# Test_board_v3.net
KiCad netlist of a schematic drawn in EAGLE
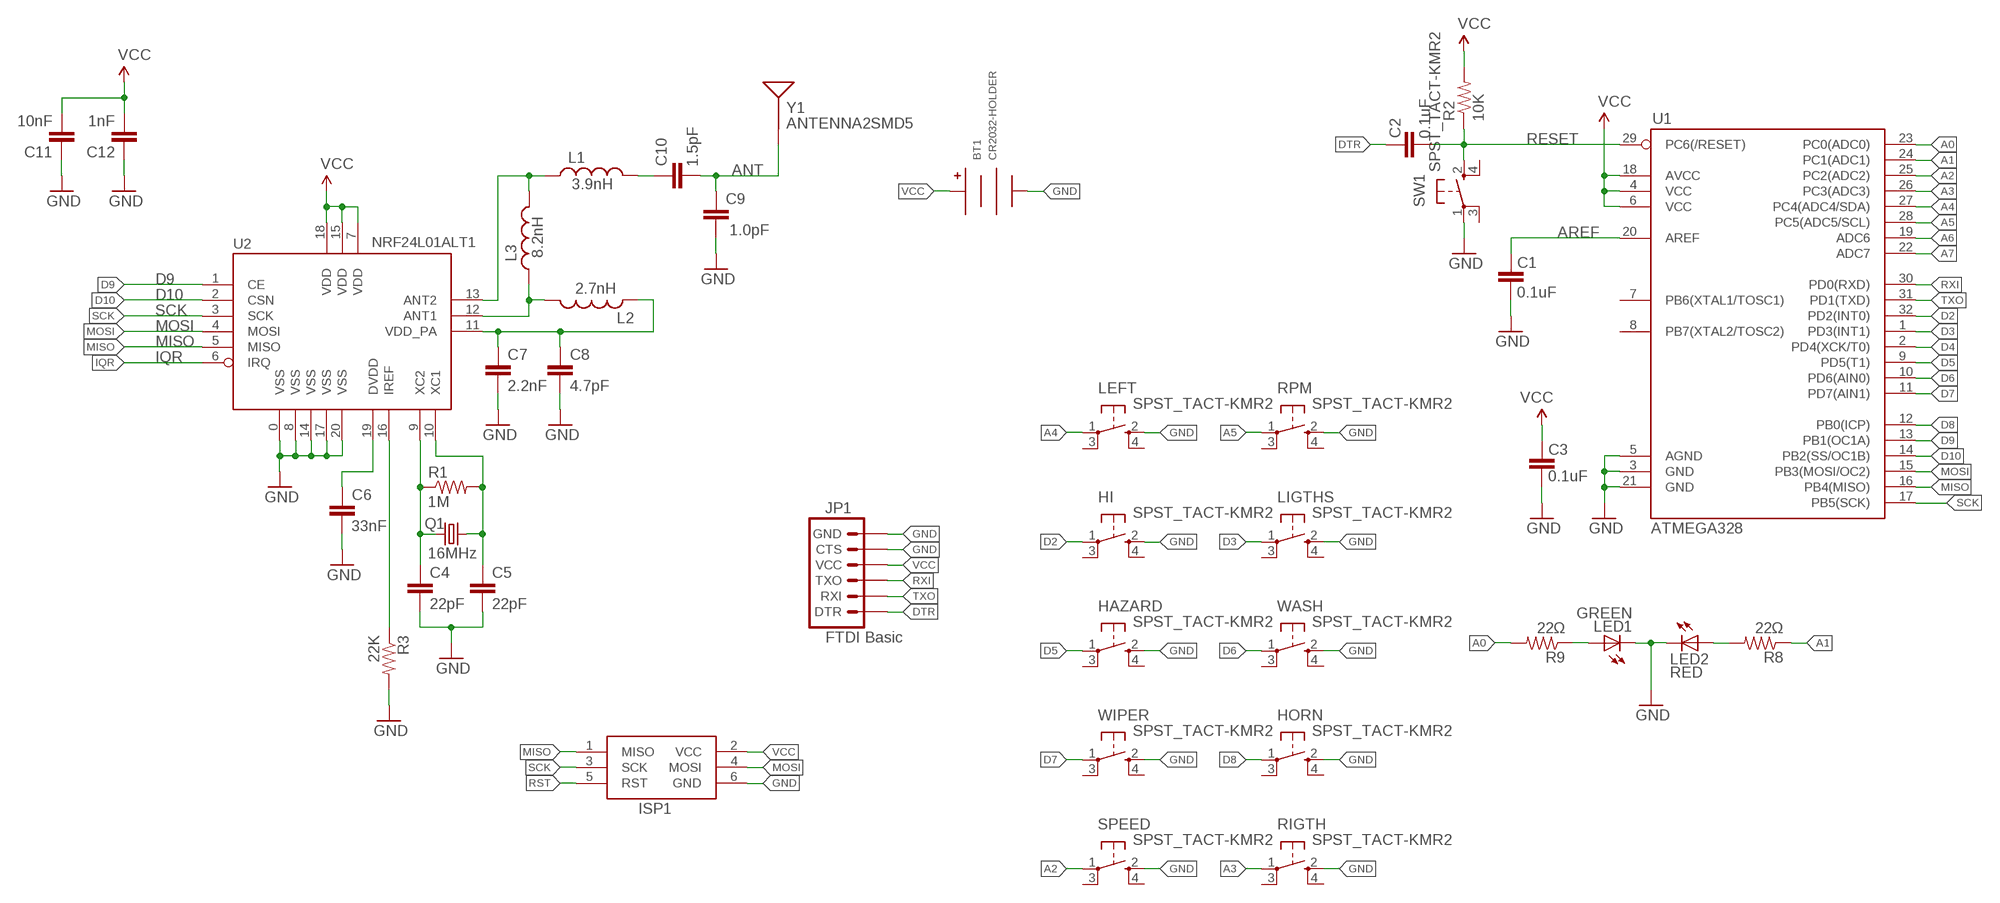
[diagram p0: schematic, sheet 1]

(export (version "E")
  (design (tool "Eeschema 10.0.6"))
  (components
    (comp (ref "BT1")
      (value "CR2032-HOLDER")
      (footprint "eagle-import:CH28-2032LF")
      (libsource (lib "eagle-import") (part "CR2032-HOLDER"))
    )
    (comp (ref "C1")
      (value "0.1uF")
      (footprint "eagle-import:0402-CAP")
      (libsource (lib "eagle-import") (part "CAP0402-CAP"))
    )
    (comp (ref "C2")
      (value "0.1uF")
      (footprint "eagle-import:0402-CAP")
      (libsource (lib "eagle-import") (part "CAP0402-CAP"))
    )
    (comp (ref "C3")
      (value "0.1uF")
      (footprint "eagle-import:0402-CAP")
      (libsource (lib "eagle-import") (part "CAP0402-CAP"))
    )
    (comp (ref "C4")
      (value "22pF")
      (footprint "eagle-import:0402-CAP")
      (libsource (lib "eagle-import") (part "CAP0402-CAP"))
    )
    (comp (ref "C5")
      (value "22pF")
      (footprint "eagle-import:0402-CAP")
      (libsource (lib "eagle-import") (part "CAP0402-CAP"))
    )
    (comp (ref "C6")
      (value "33nF")
      (footprint "eagle-import:0402-CAP")
      (libsource (lib "eagle-import") (part "CAP0402-CAP"))
    )
    (comp (ref "C7")
      (value "2.2nF")
      (footprint "eagle-import:0402-CAP")
      (libsource (lib "eagle-import") (part "CAP0402-CAP"))
    )
    (comp (ref "C8")
      (value "4.7pF")
      (footprint "eagle-import:0402-CAP")
      (libsource (lib "eagle-import") (part "CAP0402-CAP"))
    )
    (comp (ref "C9")
      (value "1.0pF")
      (footprint "eagle-import:0402-CAP")
      (libsource (lib "eagle-import") (part "CAP0402-CAP"))
    )
    (comp (ref "C10")
      (value "1.5pF")
      (footprint "eagle-import:0402-CAP")
      (libsource (lib "eagle-import") (part "CAP0402-CAP"))
    )
    (comp (ref "C11")
      (value "10nF")
      (footprint "eagle-import:0402-CAP")
      (libsource (lib "eagle-import") (part "CAP0402-CAP"))
    )
    (comp (ref "C12")
      (value "1nF")
      (footprint "eagle-import:0402-CAP")
      (libsource (lib "eagle-import") (part "CAP0402-CAP"))
    )
    (comp (ref "HAZARD")
      (value "SPST_TACT-KMR2")
      (footprint "eagle-import:KMR2")
      (libsource (lib "eagle-import") (part "SPST_TACT-KMR2"))
    )
    (comp (ref "HI")
      (value "SPST_TACT-KMR2")
      (footprint "eagle-import:KMR2")
      (libsource (lib "eagle-import") (part "SPST_TACT-KMR2"))
    )
    (comp (ref "HORN")
      (value "SPST_TACT-KMR2")
      (footprint "eagle-import:KMR2")
      (libsource (lib "eagle-import") (part "SPST_TACT-KMR2"))
    )
    (comp (ref "ISP1")
      (value "AVRISP-6")
      (footprint "eagle-import:AVRISP")
      (libsource (lib "eagle-import") (part "AVRISP-6"))
    )
    (comp (ref "JP1")
      (value "FTDI Basic")
      (footprint "eagle-import:1X06")
      (libsource (lib "eagle-import") (part "ARDUINO_SERIAL_PROGRAMPTH"))
    )
    (comp (ref "L1")
      (value "3.9nH")
      (footprint "eagle-import:C0402")
      (libsource (lib "eagle-import") (part "INDUCTOR0402"))
    )
    (comp (ref "L2")
      (value "2.7nH")
      (footprint "eagle-import:C0402")
      (libsource (lib "eagle-import") (part "INDUCTOR0402"))
    )
    (comp (ref "L3")
      (value "8.2nH")
      (footprint "eagle-import:C0402")
      (libsource (lib "eagle-import") (part "INDUCTOR0402"))
    )
    (comp (ref "LED1")
      (value "GREEN")
      (footprint "eagle-import:CHIP-LED0603")
      (libsource (lib "eagle-import") (part "LEDCHIP-LED0603"))
    )
    (comp (ref "LED2")
      (value "RED")
      (footprint "eagle-import:CHIP-LED0603")
      (libsource (lib "eagle-import") (part "LEDCHIP-LED0603"))
    )
    (comp (ref "LEFT")
      (value "SPST_TACT-KMR2")
      (footprint "eagle-import:KMR2")
      (libsource (lib "eagle-import") (part "SPST_TACT-KMR2"))
    )
    (comp (ref "LIGTHS")
      (value "SPST_TACT-KMR2")
      (footprint "eagle-import:KMR2")
      (libsource (lib "eagle-import") (part "SPST_TACT-KMR2"))
    )
    (comp (ref "Q1")
      (value "16MHz")
      (footprint "eagle-import:CRYSTAL-SMD-5X3")
      (libsource (lib "eagle-import") (part "CRYSTAL5X3"))
    )
    (comp (ref "R1")
      (value "1M")
      (footprint "eagle-import:0402-RES")
      (libsource (lib "eagle-import") (part "RESISTOR0402-RES"))
    )
    (comp (ref "R2")
      (value "10K")
      (footprint "eagle-import:0402-RES")
      (libsource (lib "eagle-import") (part "RESISTOR0402-RES"))
    )
    (comp (ref "R3")
      (value "22K")
      (footprint "eagle-import:0402-RES")
      (libsource (lib "eagle-import") (part "RESISTOR0402-RES"))
    )
    (comp (ref "R8")
      (value "22Ω")
      (footprint "eagle-import:R0402")
      (libsource (lib "eagle-import") (part "R-US_R0402"))
    )
    (comp (ref "R9")
      (value "22Ω")
      (footprint "eagle-import:R0402")
      (libsource (lib "eagle-import") (part "R-US_R0402"))
    )
    (comp (ref "RIGTH")
      (value "SPST_TACT-KMR2")
      (footprint "eagle-import:KMR2")
      (libsource (lib "eagle-import") (part "SPST_TACT-KMR2"))
    )
    (comp (ref "RPM")
      (value "SPST_TACT-KMR2")
      (footprint "eagle-import:KMR2")
      (libsource (lib "eagle-import") (part "SPST_TACT-KMR2"))
    )
    (comp (ref "SPEED")
      (value "SPST_TACT-KMR2")
      (footprint "eagle-import:KMR2")
      (libsource (lib "eagle-import") (part "SPST_TACT-KMR2"))
    )
    (comp (ref "SW1")
      (value "SPST_TACT-KMR2")
      (footprint "eagle-import:KMR2")
      (libsource (lib "eagle-import") (part "SPST_TACT-KMR2"))
    )
    (comp (ref "U1")
      (value "ATMEGA328")
      (footprint "eagle-import:TQFP32-08")
      (libsource (lib "eagle-import") (part "ATMEGA168"))
    )
    (comp (ref "U2")
      (value "NRF24L01ALT1")
      (footprint "eagle-import:QFN20_ALT1")
      (libsource (lib "eagle-import") (part "NRF24L01ALT1"))
    )
    (comp (ref "WASH")
      (value "SPST_TACT-KMR2")
      (footprint "eagle-import:KMR2")
      (libsource (lib "eagle-import") (part "SPST_TACT-KMR2"))
    )
    (comp (ref "WIPER")
      (value "SPST_TACT-KMR2")
      (footprint "eagle-import:KMR2")
      (libsource (lib "eagle-import") (part "SPST_TACT-KMR2"))
    )
    (comp (ref "Y1")
      (value "ANTENNA2SMD5")
      (footprint "eagle-import:ANTENNA-CHIP5")
      (libsource (lib "eagle-import") (part "ANTENNA2SMD5"))
    )
  )
  (nets
    (net (code "1") (name "/ANT") (class "Default")
      (node (ref "C10") (pin "2") (pinfunction "2_2") (pintype "passive"))
      (node (ref "C9") (pin "2") (pinfunction "2_2") (pintype "passive"))
      (node (ref "Y1") (pin "FEED") (pinfunction "SIGNAL_FEED") (pintype "bidirectional"))
    )
    (net (code "2") (name "/AREF") (class "Default")
      (node (ref "C1") (pin "2") (pinfunction "2_2") (pintype "passive"))
      (node (ref "U1") (pin "20") (pinfunction "AREF_20") (pintype "bidirectional"))
    )
    (net (code "3") (name "/RESET") (class "Default")
      (node (ref "C2") (pin "1") (pinfunction "1_1") (pintype "passive"))
      (node (ref "R2") (pin "1") (pinfunction "1_1") (pintype "passive"))
      (node (ref "SW1") (pin "2") (pinfunction "S_2") (pintype "passive"))
      (node (ref "U1") (pin "29") (pinfunction "PC6(/RESET)_29") (pintype "bidirectional"))
    )
    (net (code "4") (name "A0") (class "Default")
      (node (ref "R9") (pin "2") (pinfunction "2_2") (pintype "passive"))
      (node (ref "U1") (pin "23") (pinfunction "PC0(ADC0)_23") (pintype "bidirectional"))
    )
    (net (code "5") (name "A1") (class "Default")
      (node (ref "R8") (pin "1") (pinfunction "1_1") (pintype "passive"))
      (node (ref "U1") (pin "24") (pinfunction "PC1(ADC1)_24") (pintype "bidirectional"))
    )
    (net (code "6") (name "A2") (class "Default")
      (node (ref "SPEED") (pin "1") (pinfunction "P_1") (pintype "passive"))
      (node (ref "U1") (pin "25") (pinfunction "PC2(ADC2)_25") (pintype "bidirectional"))
    )
    (net (code "7") (name "A3") (class "Default")
      (node (ref "RIGTH") (pin "1") (pinfunction "P_1") (pintype "passive"))
      (node (ref "U1") (pin "26") (pinfunction "PC3(ADC3)_26") (pintype "bidirectional"))
    )
    (net (code "8") (name "A4") (class "Default")
      (node (ref "LEFT") (pin "1") (pinfunction "P_1") (pintype "passive"))
      (node (ref "U1") (pin "27") (pinfunction "PC4(ADC4/SDA)_27") (pintype "bidirectional"))
    )
    (net (code "9") (name "A5") (class "Default")
      (node (ref "RPM") (pin "1") (pinfunction "P_1") (pintype "passive"))
      (node (ref "U1") (pin "28") (pinfunction "PC5(ADC5/SCL)_28") (pintype "bidirectional"))
    )
    (net (code "10") (name "A6") (class "Default")
      (node (ref "U1") (pin "19") (pinfunction "ADC6_19") (pintype "bidirectional"))
    )
    (net (code "11") (name "A7") (class "Default")
      (node (ref "U1") (pin "22") (pinfunction "ADC7_22") (pintype "bidirectional"))
    )
    (net (code "12") (name "D2") (class "Default")
      (node (ref "HI") (pin "1") (pinfunction "P_1") (pintype "passive"))
      (node (ref "U1") (pin "32") (pinfunction "PD2(INT0)_32") (pintype "bidirectional"))
    )
    (net (code "13") (name "D3") (class "Default")
      (node (ref "LIGTHS") (pin "1") (pinfunction "P_1") (pintype "passive"))
      (node (ref "U1") (pin "1") (pinfunction "PD3(INT1)_1") (pintype "bidirectional"))
    )
    (net (code "14") (name "D4") (class "Default")
      (node (ref "U1") (pin "2") (pinfunction "PD4(XCK/T0)_2") (pintype "bidirectional"))
    )
    (net (code "15") (name "D5") (class "Default")
      (node (ref "HAZARD") (pin "1") (pinfunction "P_1") (pintype "passive"))
      (node (ref "U1") (pin "9") (pinfunction "PD5(T1)_9") (pintype "bidirectional"))
    )
    (net (code "16") (name "D6") (class "Default")
      (node (ref "U1") (pin "10") (pinfunction "PD6(AIN0)_10") (pintype "bidirectional"))
      (node (ref "WASH") (pin "1") (pinfunction "P_1") (pintype "passive"))
    )
    (net (code "17") (name "D7") (class "Default")
      (node (ref "U1") (pin "11") (pinfunction "PD7(AIN1)_11") (pintype "bidirectional"))
      (node (ref "WIPER") (pin "1") (pinfunction "P_1") (pintype "passive"))
    )
    (net (code "18") (name "D8") (class "Default")
      (node (ref "HORN") (pin "1") (pinfunction "P_1") (pintype "passive"))
      (node (ref "U1") (pin "12") (pinfunction "PB0(ICP)_12") (pintype "bidirectional"))
    )
    (net (code "19") (name "D9") (class "Default")
      (node (ref "U1") (pin "13") (pinfunction "PB1(OC1A)_13") (pintype "bidirectional"))
      (node (ref "U2") (pin "1") (pinfunction "CE_1") (pintype "input"))
    )
    (net (code "20") (name "D10") (class "Default")
      (node (ref "U1") (pin "14") (pinfunction "PB2(SS/OC1B)_14") (pintype "bidirectional"))
      (node (ref "U2") (pin "2") (pinfunction "CSN_2") (pintype "input"))
    )
    (net (code "21") (name "DTR") (class "Default")
      (node (ref "C2") (pin "2") (pinfunction "2_2") (pintype "passive"))
      (node (ref "JP1") (pin "1") (pinfunction "DTR_1") (pintype "passive"))
    )
    (net (code "22") (name "GND") (class "Default")
      (node (ref "BT1") (pin "NEG") (pinfunction "NEG_NEG") (pintype "bidirectional"))
      (node (ref "C1") (pin "1") (pinfunction "1_1") (pintype "passive"))
      (node (ref "C11") (pin "1") (pinfunction "1_1") (pintype "passive"))
      (node (ref "C12") (pin "1") (pinfunction "1_1") (pintype "passive"))
      (node (ref "C3") (pin "1") (pinfunction "1_1") (pintype "passive"))
      (node (ref "C4") (pin "2") (pinfunction "2_2") (pintype "passive"))
      (node (ref "C5") (pin "2") (pinfunction "2_2") (pintype "passive"))
      (node (ref "C6") (pin "2") (pinfunction "2_2") (pintype "passive"))
      (node (ref "C7") (pin "2") (pinfunction "2_2") (pintype "passive"))
      (node (ref "C8") (pin "2") (pinfunction "2_2") (pintype "passive"))
      (node (ref "C9") (pin "1") (pinfunction "1_1") (pintype "passive"))
      (node (ref "HAZARD") (pin "2") (pinfunction "S_2") (pintype "passive"))
      (node (ref "HI") (pin "2") (pinfunction "S_2") (pintype "passive"))
      (node (ref "HORN") (pin "2") (pinfunction "S_2") (pintype "passive"))
      (node (ref "ISP1") (pin "6") (pinfunction "GND_6") (pintype "power_in"))
      (node (ref "JP1") (pin "5") (pinfunction "CTS_5") (pintype "passive"))
      (node (ref "JP1") (pin "6") (pinfunction "GND_6") (pintype "passive"))
      (node (ref "LED1") (pin "C") (pinfunction "C_C") (pintype "passive"))
      (node (ref "LED2") (pin "C") (pinfunction "C_C") (pintype "passive"))
      (node (ref "LEFT") (pin "2") (pinfunction "S_2") (pintype "passive"))
      (node (ref "LIGTHS") (pin "2") (pinfunction "S_2") (pintype "passive"))
      (node (ref "R3") (pin "2") (pinfunction "2_2") (pintype "passive"))
      (node (ref "RIGTH") (pin "2") (pinfunction "S_2") (pintype "passive"))
      (node (ref "RPM") (pin "2") (pinfunction "S_2") (pintype "passive"))
      (node (ref "SPEED") (pin "2") (pinfunction "S_2") (pintype "passive"))
      (node (ref "SW1") (pin "1") (pinfunction "P_1") (pintype "passive"))
      (node (ref "U1") (pin "21") (pinfunction "GND_21") (pintype "bidirectional"))
      (node (ref "U1") (pin "3") (pinfunction "GND_3") (pintype "bidirectional"))
      (node (ref "U1") (pin "5") (pinfunction "AGND_5") (pintype "bidirectional"))
      (node (ref "U2") (pin "0") (pinfunction "VSS_0") (pintype "power_in"))
      (node (ref "U2") (pin "14") (pinfunction "VSS_14") (pintype "power_in"))
      (node (ref "U2") (pin "17") (pinfunction "VSS_17") (pintype "power_in"))
      (node (ref "U2") (pin "20") (pinfunction "VSS_20") (pintype "power_in"))
      (node (ref "U2") (pin "8") (pinfunction "VSS_8") (pintype "power_in"))
      (node (ref "WASH") (pin "2") (pinfunction "S_2") (pintype "passive"))
      (node (ref "WIPER") (pin "2") (pinfunction "S_2") (pintype "passive"))
    )
    (net (code "23") (name "IQR") (class "Default")
      (node (ref "U2") (pin "6") (pinfunction "IRQ_6") (pintype "output"))
    )
    (net (code "24") (name "MISO") (class "Default")
      (node (ref "ISP1") (pin "1") (pinfunction "MISO_1") (pintype "input"))
      (node (ref "U1") (pin "16") (pinfunction "PB4(MISO)_16") (pintype "bidirectional"))
      (node (ref "U2") (pin "5") (pinfunction "MISO_5") (pintype "output"))
    )
    (net (code "25") (name "MOSI") (class "Default")
      (node (ref "ISP1") (pin "4") (pinfunction "MOSI_4") (pintype "output"))
      (node (ref "U1") (pin "15") (pinfunction "PB3(MOSI/OC2)_15") (pintype "bidirectional"))
      (node (ref "U2") (pin "4") (pinfunction "MOSI_4") (pintype "input"))
    )
    (net (code "26") (name "Net-(C10-Pad1)") (class "Default")
      (node (ref "C10") (pin "1") (pinfunction "1_1") (pintype "passive"))
      (node (ref "L1") (pin "2") (pinfunction "2_2") (pintype "passive"))
    )
    (net (code "27") (name "Net-(LED1-PadA)") (class "Default")
      (node (ref "LED1") (pin "A") (pinfunction "A_A") (pintype "passive"))
      (node (ref "R9") (pin "1") (pinfunction "1_1") (pintype "passive"))
    )
    (net (code "28") (name "Net-(LED2-PadA)") (class "Default")
      (node (ref "LED2") (pin "A") (pinfunction "A_A") (pintype "passive"))
      (node (ref "R8") (pin "2") (pinfunction "2_2") (pintype "passive"))
    )
    (net (code "29") (name "Net-(Q1-2)") (class "Default")
      (node (ref "C5") (pin "1") (pinfunction "1_1") (pintype "passive"))
      (node (ref "Q1") (pin "3") (pinfunction "2_3") (pintype "passive"))
      (node (ref "R1") (pin "2") (pinfunction "2_2") (pintype "passive"))
      (node (ref "U2") (pin "10") (pinfunction "XC1_10") (pintype "input"))
    )
    (net (code "30") (name "Net-(U2-ANT1)") (class "Default")
      (node (ref "L2") (pin "2") (pinfunction "2_2") (pintype "passive"))
      (node (ref "L3") (pin "1") (pinfunction "1_1") (pintype "passive"))
      (node (ref "U2") (pin "12") (pinfunction "ANT1_12") (pintype "output"))
    )
    (net (code "31") (name "Net-(U2-ANT2)") (class "Default")
      (node (ref "L1") (pin "1") (pinfunction "1_1") (pintype "passive"))
      (node (ref "L3") (pin "2") (pinfunction "2_2") (pintype "passive"))
      (node (ref "U2") (pin "13") (pinfunction "ANT2_13") (pintype "output"))
    )
    (net (code "32") (name "Net-(U2-DVDD)") (class "Default")
      (node (ref "C6") (pin "1") (pinfunction "1_1") (pintype "passive"))
      (node (ref "U2") (pin "19") (pinfunction "DVDD_19") (pintype "power_in"))
    )
    (net (code "33") (name "Net-(U2-IREF)") (class "Default")
      (node (ref "R3") (pin "1") (pinfunction "1_1") (pintype "passive"))
      (node (ref "U2") (pin "16") (pinfunction "IREF_16") (pintype "input"))
    )
    (net (code "34") (name "Net-(U2-VDD_PA)") (class "Default")
      (node (ref "C7") (pin "1") (pinfunction "1_1") (pintype "passive"))
      (node (ref "C8") (pin "1") (pinfunction "1_1") (pintype "passive"))
      (node (ref "L2") (pin "1") (pinfunction "1_1") (pintype "passive"))
      (node (ref "U2") (pin "11") (pinfunction "VDD_PA_11") (pintype "power_in"))
    )
    (net (code "35") (name "Net-(U2-XC2)") (class "Default")
      (node (ref "C4") (pin "1") (pinfunction "1_1") (pintype "passive"))
      (node (ref "Q1") (pin "1") (pinfunction "1_1") (pintype "passive"))
      (node (ref "R1") (pin "1") (pinfunction "1_1") (pintype "passive"))
      (node (ref "U2") (pin "9") (pinfunction "XC2_9") (pintype "input"))
    )
    (net (code "36") (name "RST") (class "Default")
      (node (ref "ISP1") (pin "5") (pinfunction "RST_5") (pintype "output"))
    )
    (net (code "37") (name "RXI") (class "Default")
      (node (ref "JP1") (pin "3") (pinfunction "TXO_3") (pintype "passive"))
      (node (ref "U1") (pin "30") (pinfunction "PD0(RXD)_30") (pintype "bidirectional"))
    )
    (net (code "38") (name "SCK") (class "Default")
      (node (ref "ISP1") (pin "3") (pinfunction "SCK_3") (pintype "output"))
      (node (ref "U1") (pin "17") (pinfunction "PB5(SCK)_17") (pintype "bidirectional"))
      (node (ref "U2") (pin "3") (pinfunction "SCK_3") (pintype "input"))
    )
    (net (code "39") (name "TXO") (class "Default")
      (node (ref "JP1") (pin "2") (pinfunction "RXI_2") (pintype "passive"))
      (node (ref "U1") (pin "31") (pinfunction "PD1(TXD)_31") (pintype "bidirectional"))
    )
    (net (code "40") (name "VCC") (class "Default")
      (node (ref "BT1") (pin "POS") (pinfunction "POS_POS") (pintype "bidirectional"))
      (node (ref "C11") (pin "2") (pinfunction "2_2") (pintype "passive"))
      (node (ref "C12") (pin "2") (pinfunction "2_2") (pintype "passive"))
      (node (ref "C3") (pin "2") (pinfunction "2_2") (pintype "passive"))
      (node (ref "ISP1") (pin "2") (pinfunction "VCC_2") (pintype "power_in"))
      (node (ref "JP1") (pin "4") (pinfunction "VCC_4") (pintype "passive"))
      (node (ref "R2") (pin "2") (pinfunction "2_2") (pintype "passive"))
      (node (ref "U1") (pin "18") (pinfunction "AVCC_18") (pintype "bidirectional"))
      (node (ref "U1") (pin "4") (pinfunction "VCC_4") (pintype "bidirectional"))
      (node (ref "U1") (pin "6") (pinfunction "VCC_6") (pintype "bidirectional"))
      (node (ref "U2") (pin "15") (pinfunction "VDD_15") (pintype "power_in"))
      (node (ref "U2") (pin "18") (pinfunction "VDD_18") (pintype "power_in"))
      (node (ref "U2") (pin "7") (pinfunction "VDD_7") (pintype "power_in"))
    )
    (net (code "41") (name "unconnected-(HAZARD-P1-Pad3)") (class "Default")
      (node (ref "HAZARD") (pin "3") (pinfunction "P1_3") (pintype "passive"))
    )
    (net (code "42") (name "unconnected-(HAZARD-S1-Pad4)") (class "Default")
      (node (ref "HAZARD") (pin "4") (pinfunction "S1_4") (pintype "passive"))
    )
    (net (code "43") (name "unconnected-(HI-P1-Pad3)") (class "Default")
      (node (ref "HI") (pin "3") (pinfunction "P1_3") (pintype "passive"))
    )
    (net (code "44") (name "unconnected-(HI-S1-Pad4)") (class "Default")
      (node (ref "HI") (pin "4") (pinfunction "S1_4") (pintype "passive"))
    )
    (net (code "45") (name "unconnected-(HORN-P1-Pad3)") (class "Default")
      (node (ref "HORN") (pin "3") (pinfunction "P1_3") (pintype "passive"))
    )
    (net (code "46") (name "unconnected-(HORN-S1-Pad4)") (class "Default")
      (node (ref "HORN") (pin "4") (pinfunction "S1_4") (pintype "passive"))
    )
    (net (code "47") (name "unconnected-(LEFT-P1-Pad3)") (class "Default")
      (node (ref "LEFT") (pin "3") (pinfunction "P1_3") (pintype "passive"))
    )
    (net (code "48") (name "unconnected-(LEFT-S1-Pad4)") (class "Default")
      (node (ref "LEFT") (pin "4") (pinfunction "S1_4") (pintype "passive"))
    )
    (net (code "49") (name "unconnected-(LIGTHS-P1-Pad3)") (class "Default")
      (node (ref "LIGTHS") (pin "3") (pinfunction "P1_3") (pintype "passive"))
    )
    (net (code "50") (name "unconnected-(LIGTHS-S1-Pad4)") (class "Default")
      (node (ref "LIGTHS") (pin "4") (pinfunction "S1_4") (pintype "passive"))
    )
    (net (code "51") (name "unconnected-(RIGTH-P1-Pad3)") (class "Default")
      (node (ref "RIGTH") (pin "3") (pinfunction "P1_3") (pintype "passive"))
    )
    (net (code "52") (name "unconnected-(RIGTH-S1-Pad4)") (class "Default")
      (node (ref "RIGTH") (pin "4") (pinfunction "S1_4") (pintype "passive"))
    )
    (net (code "53") (name "unconnected-(RPM-P1-Pad3)") (class "Default")
      (node (ref "RPM") (pin "3") (pinfunction "P1_3") (pintype "passive"))
    )
    (net (code "54") (name "unconnected-(RPM-S1-Pad4)") (class "Default")
      (node (ref "RPM") (pin "4") (pinfunction "S1_4") (pintype "passive"))
    )
    (net (code "55") (name "unconnected-(SPEED-P1-Pad3)") (class "Default")
      (node (ref "SPEED") (pin "3") (pinfunction "P1_3") (pintype "passive"))
    )
    (net (code "56") (name "unconnected-(SPEED-S1-Pad4)") (class "Default")
      (node (ref "SPEED") (pin "4") (pinfunction "S1_4") (pintype "passive"))
    )
    (net (code "57") (name "unconnected-(SW1-P1-Pad3)") (class "Default")
      (node (ref "SW1") (pin "3") (pinfunction "P1_3") (pintype "passive"))
    )
    (net (code "58") (name "unconnected-(SW1-S1-Pad4)") (class "Default")
      (node (ref "SW1") (pin "4") (pinfunction "S1_4") (pintype "passive"))
    )
    (net (code "59") (name "unconnected-(U1-PB6(XTAL1{slash}TOSC1)-Pad7)") (class "Default")
      (node (ref "U1") (pin "7") (pinfunction "PB6(XTAL1/TOSC1)_7") (pintype "bidirectional"))
    )
    (net (code "60") (name "unconnected-(U1-PB7(XTAL2{slash}TOSC2)-Pad8)") (class "Default")
      (node (ref "U1") (pin "8") (pinfunction "PB7(XTAL2/TOSC2)_8") (pintype "bidirectional"))
    )
    (net (code "61") (name "unconnected-(WASH-P1-Pad3)") (class "Default")
      (node (ref "WASH") (pin "3") (pinfunction "P1_3") (pintype "passive"))
    )
    (net (code "62") (name "unconnected-(WASH-S1-Pad4)") (class "Default")
      (node (ref "WASH") (pin "4") (pinfunction "S1_4") (pintype "passive"))
    )
    (net (code "63") (name "unconnected-(WIPER-P1-Pad3)") (class "Default")
      (node (ref "WIPER") (pin "3") (pinfunction "P1_3") (pintype "passive"))
    )
    (net (code "64") (name "unconnected-(WIPER-S1-Pad4)") (class "Default")
      (node (ref "WIPER") (pin "4") (pinfunction "S1_4") (pintype "passive"))
    )
  )
)
